# Power.net
KiCad netlist of a schematic drawn in Altium Designer
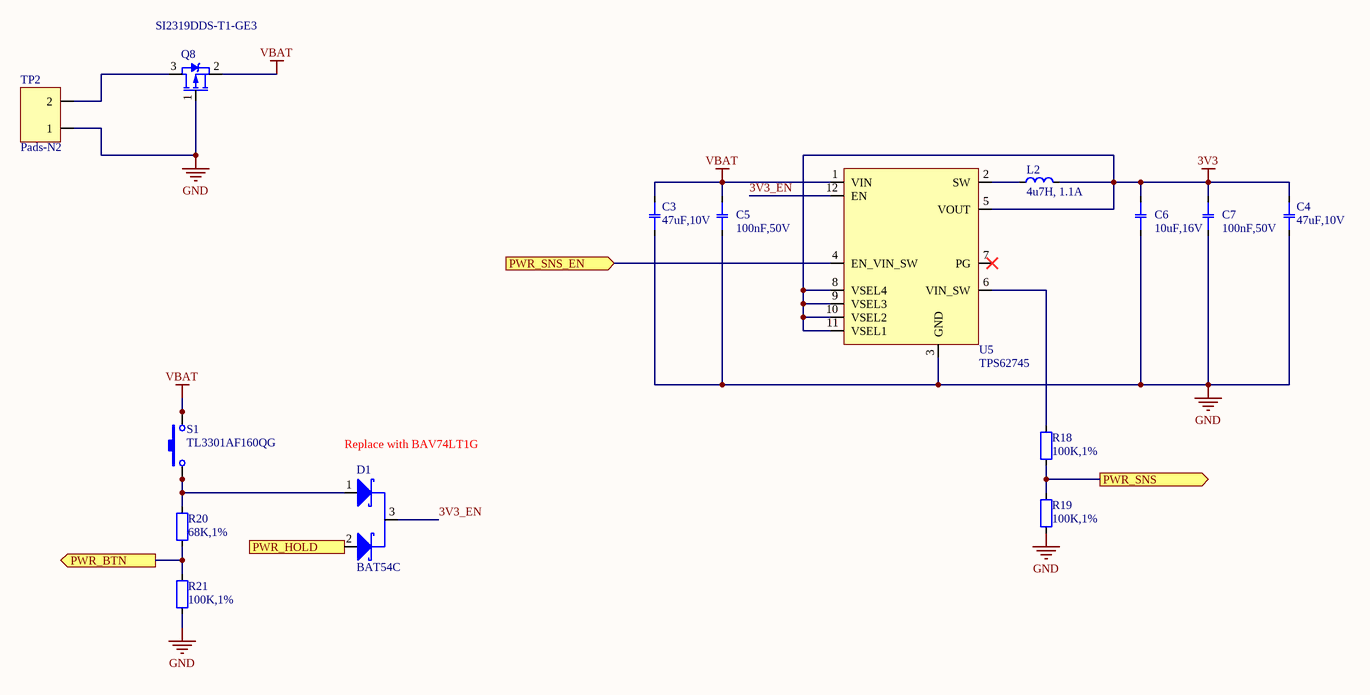
[diagram p0: Power.SchDoc]

(export (version "E")
  (design (tool "Eeschema 10.0.6"))
  (components
    (comp (ref "C3")
      (value "47uF,10V")
      (footprint "CAPC2012X12N_0805")
      (description "CAP CER 47UF 10V 20% X5R 0805")
      (fields (field (name "MANUFACTURER") "TDK Corporation") (field (name "TOLERANCE") "20%"))
      (libsource (lib "library") (part "CAP-NP_1"))
    )
    (comp (ref "C4")
      (value "47uF,10V")
      (footprint "CAPC2012X12N_0805")
      (description "CAP CER 47UF 10V 20% X5R 0805")
      (fields (field (name "MANUFACTURER") "TDK Corporation") (field (name "TOLERANCE") "20%"))
      (libsource (lib "library") (part "CAP-NP_1"))
    )
    (comp (ref "C5")
      (value "100nF,50V")
      (footprint "CAPC1608X09N_0603")
      (description "CAP CER 0.1UF 50V 10% X7R 0603")
      (fields (field (name "MANUFACTURER") "Kemet") (field (name "TOLERANCE") "10%"))
      (libsource (lib "library") (part "CAP-NP_1"))
    )
    (comp (ref "C6")
      (value "10uF,16V")
      (footprint "CAPC2012X12N_0805")
      (description "CAP CER 10µF ±10% 16V X7R 0805")
      (fields
        (field (name "MANUFACTURER") "Samsung Electro-Mechanics America, Inc.")
        (field (name "TOLERANCE") "10%")
      )
      (libsource (lib "library") (part "CAP-NP_1"))
    )
    (comp (ref "C7")
      (value "100nF,50V")
      (footprint "CAPC1608X09N_0603")
      (description "CAP CER 0.1UF 50V 10% X7R 0603")
      (fields (field (name "MANUFACTURER") "Kemet") (field (name "TOLERANCE") "10%"))
      (libsource (lib "library") (part "CAP-NP_1"))
    )
    (comp (ref "D1")
      (value "BAT54C")
      (footprint "SOT95P237X111-3N_SOT23")
      (description "DIODE ARRAY SCHOTTKY 30V SOT23-3")
      (fields (field (name "MANUFACTURER") "Fairchild/ON Semiconductor"))
      (libsource (lib "library") (part "BAT54C"))
    )
    (comp (ref "L2")
      (value "4u7H, 1.1A")
      (footprint "INDC2520X12N_1008")
      (description "INDUCTOR POWER 4.7UH 1.1A SMD")
      (fields
        (field (name "MANUFACTURER") "Murata Electronics North America")
        (field (name "MANUFACTURER PART NUMBER") "DFE252010R-H-4R7M=P2")
      )
      (libsource (lib "library") (part "INDUCTOR_1"))
    )
    (comp (ref "Q8")
      (value "SI2319DDS-T1-GE3")
      (footprint "SOT95P230X110-3N_SOT23")
      (description "MOSFET P-CHAN 40V")
      (fields (field (name "MANUFACTURER") "Vishay Siliconix"))
      (libsource (lib "library") (part "MOSFET-P_1"))
    )
    (comp (ref "R18")
      (value "100K,1%")
      (footprint "RESC1608X06N_0603")
      (description "RES 100K OHM 1/10W 1% 0603 SMD")
      (fields (field (name "MANUFACTURER") "Yageo") (field (name "POWER") "0.1W"))
      (libsource (lib "library") (part "RESISTOR_1"))
    )
    (comp (ref "R19")
      (value "100K,1%")
      (footprint "RESC1608X06N_0603")
      (description "RES 100K OHM 1/10W 1% 0603 SMD")
      (fields (field (name "MANUFACTURER") "Yageo") (field (name "POWER") "0.1W"))
      (libsource (lib "library") (part "RESISTOR_1"))
    )
    (comp (ref "R20")
      (value "68K,1%")
      (footprint "RESC1608X06N_0603")
      (description "RES 68K OHM 1/10W 1% 0603 SMD")
      (fields (field (name "MANUFACTURER") "Yageo") (field (name "POWER") "0.1W"))
      (libsource (lib "library") (part "RESISTOR_1"))
    )
    (comp (ref "R21")
      (value "100K,1%")
      (footprint "RESC1608X06N_0603")
      (description "RES 100K OHM 1/10W 1% 0603 SMD")
      (fields (field (name "MANUFACTURER") "Yageo") (field (name "POWER") "0.1W"))
      (libsource (lib "") (part "RESISTOR_1_1"))
    )
    (comp (ref "S1")
      (value "TL3301AF160QG")
      (footprint "SW_TL3301AFXXXXG")
      (description "SWITCH TACT 160GF H=5.0MM SMT")
      (fields (field (name "MANUFACTURER") "E-Switch"))
      (libsource (lib "library") (part "SW_SPST_2"))
    )
    (comp (ref "TP2") (value "Pads-N2") (footprint "PADS-N2") (libsource (lib "Common") (part "Pads-N2")))
    (comp (ref "U5")
      (value "TPS62745")
      (footprint "R-PWSON-N12")
      (description "Step Down Converter")
      (fields (field (name "MANUFACTURER") "Texas Instruments"))
      (libsource (lib "library") (part "TPS62745"))
    )
  )
  (nets
    (net (code "1") (name "/3V3_EN") (class "Default")
      (node (ref "D1") (pin "3") (pinfunction "C1/C2_3") (pintype "passive"))
      (node (ref "U5") (pin "12") (pinfunction "EN_12") (pintype "passive"))
    )
    (net (code "2") (name "/PWR_BTN") (class "Default")
      (node (ref "R20") (pin "1") (pinfunction "1_1") (pintype "passive"))
      (node (ref "R21") (pin "1") (pinfunction "1_1") (pintype "passive"))
    )
    (net (code "3") (name "/PWR_HOLD") (class "Default")
      (node (ref "D1") (pin "2") (pinfunction "A2_2") (pintype "passive"))
    )
    (net (code "4") (name "/PWR_SNS") (class "Default")
      (node (ref "R18") (pin "1") (pinfunction "1_1") (pintype "passive"))
      (node (ref "R19") (pin "2") (pinfunction "2_2") (pintype "passive"))
    )
    (net (code "5") (name "/PWR_SNS_EN") (class "Default")
      (node (ref "U5") (pin "4") (pinfunction "EN_VIN_SW_4") (pintype "passive"))
    )
    (net (code "6") (name "3V3") (class "Default")
      (node (ref "C4") (pin "1") (pinfunction "1_1") (pintype "passive"))
      (node (ref "C6") (pin "2") (pinfunction "2_2") (pintype "passive"))
      (node (ref "C7") (pin "2") (pinfunction "2_2") (pintype "passive"))
      (node (ref "L2") (pin "2") (pinfunction "2_2") (pintype "passive"))
      (node (ref "U5") (pin "10") (pinfunction "VSEL2_10") (pintype "passive"))
      (node (ref "U5") (pin "11") (pinfunction "VSEL1_11") (pintype "passive"))
      (node (ref "U5") (pin "5") (pinfunction "VOUT_5") (pintype "passive"))
      (node (ref "U5") (pin "8") (pinfunction "VSEL4_8") (pintype "passive"))
      (node (ref "U5") (pin "9") (pinfunction "VSEL3_9") (pintype "passive"))
    )
    (net (code "7") (name "GND") (class "Default")
      (node (ref "C3") (pin "2") (pinfunction "2_2") (pintype "passive"))
      (node (ref "C4") (pin "2") (pinfunction "2_2") (pintype "passive"))
      (node (ref "C5") (pin "1") (pinfunction "1_1") (pintype "passive"))
      (node (ref "C6") (pin "1") (pinfunction "1_1") (pintype "passive"))
      (node (ref "C7") (pin "1") (pinfunction "1_1") (pintype "passive"))
      (node (ref "Q8") (pin "1") (pinfunction "G_1") (pintype "passive"))
      (node (ref "R19") (pin "1") (pinfunction "1_1") (pintype "passive"))
      (node (ref "R21") (pin "2") (pinfunction "2_2") (pintype "passive"))
      (node (ref "TP2") (pin "1") (pinfunction "1_1") (pintype "passive"))
      (node (ref "U5") (pin "3") (pinfunction "GND_3") (pintype "passive"))
    )
    (net (code "8") (name "Net-(D1-A1)") (class "Default")
      (node (ref "D1") (pin "1") (pinfunction "A1_1") (pintype "passive"))
      (node (ref "R20") (pin "2") (pinfunction "2_2") (pintype "passive"))
      (node (ref "S1") (pin "1") (pinfunction "1_1") (pintype "passive"))
      (node (ref "S1") (pin "2") (pinfunction "2_2") (pintype "passive"))
    )
    (net (code "9") (name "Net-(Q8-D)") (class "Default")
      (node (ref "Q8") (pin "3") (pinfunction "D_3") (pintype "passive"))
      (node (ref "TP2") (pin "2") (pinfunction "2_2") (pintype "passive"))
    )
    (net (code "10") (name "Net-(U5-SW)") (class "Default")
      (node (ref "L2") (pin "1") (pinfunction "1_1") (pintype "passive"))
      (node (ref "U5") (pin "2") (pinfunction "SW_2") (pintype "passive"))
    )
    (net (code "11") (name "Net-(U5-VIN_SW)") (class "Default")
      (node (ref "R18") (pin "2") (pinfunction "2_2") (pintype "passive"))
      (node (ref "U5") (pin "6") (pinfunction "VIN_SW_6") (pintype "passive"))
    )
    (net (code "12") (name "VBAT") (class "Default")
      (node (ref "C3") (pin "1") (pinfunction "1_1") (pintype "passive"))
      (node (ref "C5") (pin "2") (pinfunction "2_2") (pintype "passive"))
      (node (ref "Q8") (pin "2") (pinfunction "S_2") (pintype "passive"))
      (node (ref "S1") (pin "3") (pinfunction "3_3") (pintype "passive"))
      (node (ref "S1") (pin "4") (pinfunction "4_4") (pintype "passive"))
      (node (ref "U5") (pin "1") (pinfunction "VIN_1") (pintype "passive"))
    )
    (net (code "13") (name "unconnected-(U5-PG-Pad7)") (class "Default")
      (node (ref "U5") (pin "7") (pinfunction "PG_7") (pintype "passive+no_connect"))
    )
  )
)
